# Sheet1.net
KiCad netlist of a schematic drawn in Altium Designer
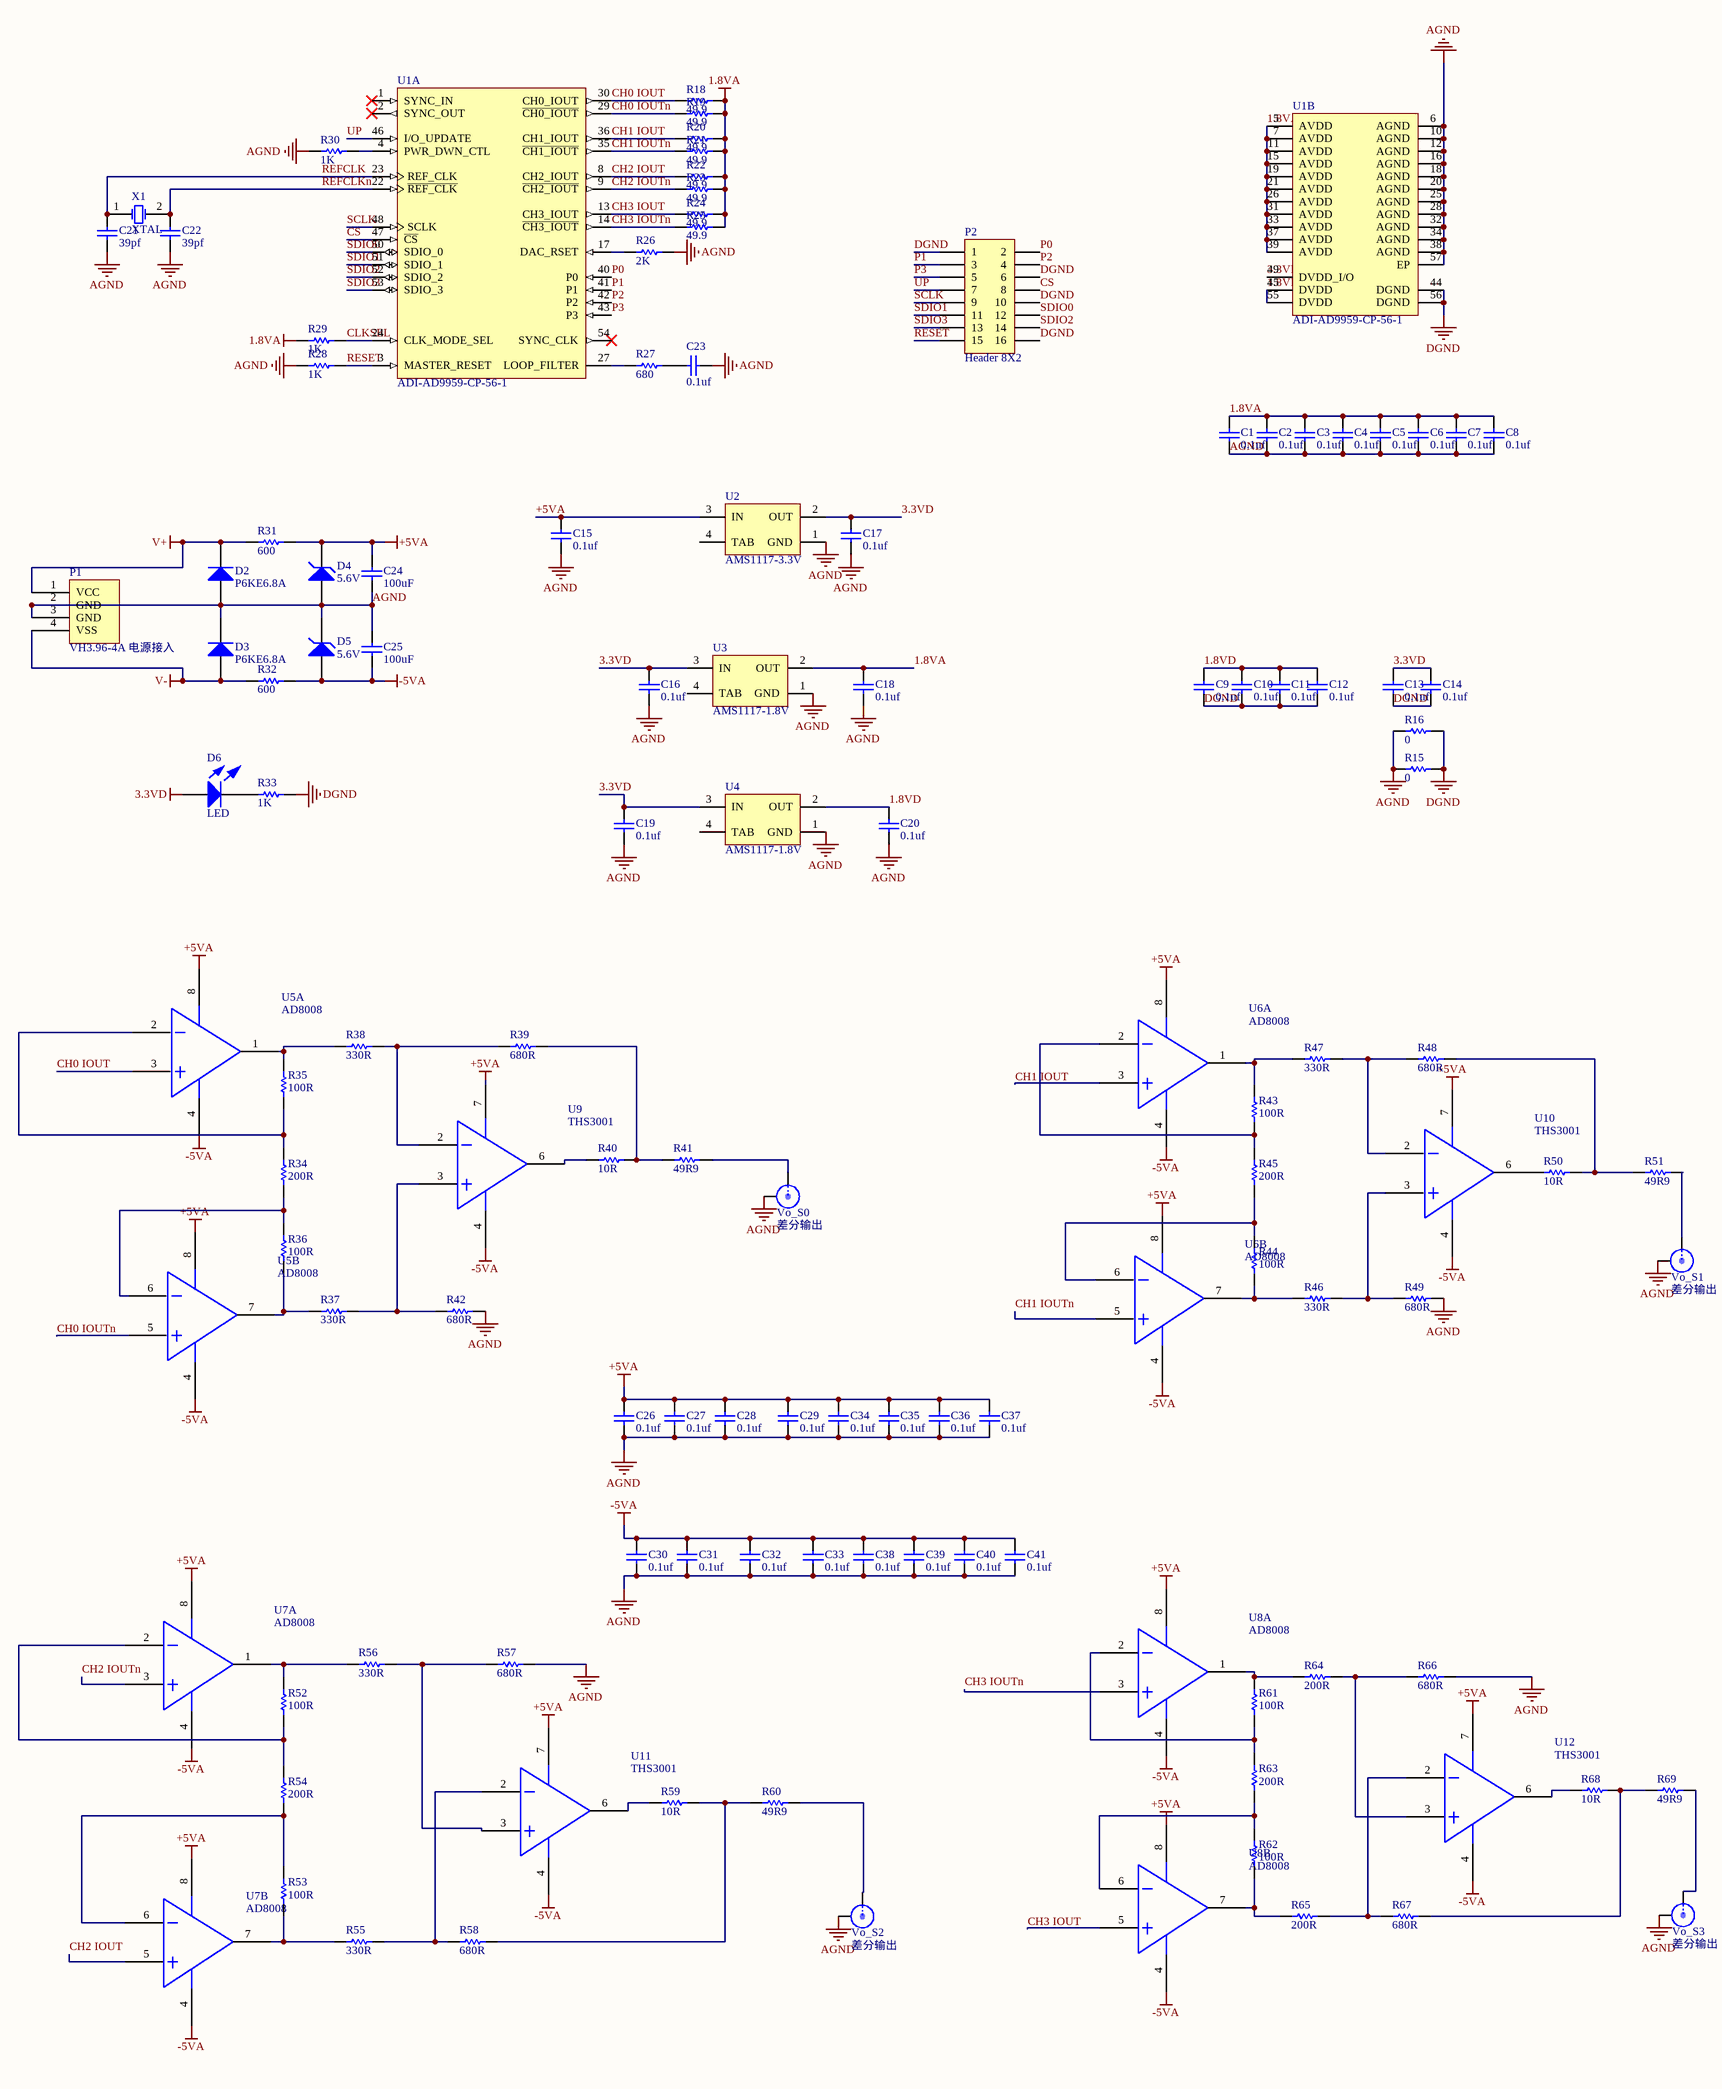
[diagram p0: Sheet1.SchDoc]

(export (version "E")
  (design (tool "Eeschema 10.0.6"))
  (components
    (comp (ref "C1") (value "0.1uf") (footprint "0805") (libsource (lib "Schlib1") (part "Cap")))
    (comp (ref "C2") (value "0.1uf") (footprint "0805") (libsource (lib "Schlib1") (part "Cap")))
    (comp (ref "C3") (value "0.1uf") (footprint "0805") (libsource (lib "Schlib1") (part "Cap")))
    (comp (ref "C4") (value "0.1uf") (footprint "0805") (libsource (lib "Schlib1") (part "Cap")))
    (comp (ref "C5") (value "0.1uf") (footprint "0805") (libsource (lib "Schlib1") (part "Cap")))
    (comp (ref "C6") (value "0.1uf") (footprint "0805") (libsource (lib "Schlib1") (part "Cap")))
    (comp (ref "C7") (value "0.1uf") (footprint "0805") (libsource (lib "Schlib1") (part "Cap")))
    (comp (ref "C8") (value "0.1uf") (footprint "0805") (libsource (lib "Schlib1") (part "Cap")))
    (comp (ref "C9") (value "0.1uf") (footprint "0805") (libsource (lib "Schlib1") (part "Cap")))
    (comp (ref "C10") (value "0.1uf") (footprint "0805") (libsource (lib "Schlib1") (part "Cap")))
    (comp (ref "C11") (value "0.1uf") (footprint "0805") (libsource (lib "Schlib1") (part "Cap")))
    (comp (ref "C12") (value "0.1uf") (footprint "0805") (libsource (lib "Schlib1") (part "Cap")))
    (comp (ref "C13") (value "0.1uf") (footprint "0805") (libsource (lib "Schlib1") (part "Cap")))
    (comp (ref "C14") (value "0.1uf") (footprint "0805") (libsource (lib "Schlib1") (part "Cap")))
    (comp (ref "C15") (value "0.1uf") (footprint "0805") (libsource (lib "Schlib1") (part "Cap")))
    (comp (ref "C16") (value "0.1uf") (footprint "0805") (libsource (lib "Schlib1") (part "Cap")))
    (comp (ref "C17") (value "0.1uf") (footprint "0805") (libsource (lib "Schlib1") (part "Cap")))
    (comp (ref "C18") (value "0.1uf") (footprint "0805") (libsource (lib "Schlib1") (part "Cap")))
    (comp (ref "C19") (value "0.1uf") (footprint "0805") (libsource (lib "Schlib1") (part "Cap")))
    (comp (ref "C20") (value "0.1uf") (footprint "0805") (libsource (lib "Schlib1") (part "Cap")))
    (comp (ref "C21") (value "39pf") (footprint "0805") (libsource (lib "Schlib1") (part "Cap")))
    (comp (ref "C22") (value "39pf") (footprint "0805") (libsource (lib "Schlib1") (part "Cap")))
    (comp (ref "C23") (value "0.1uf") (footprint "0805") (libsource (lib "Schlib1") (part "Cap")))
    (comp (ref "C24") (value "100uF") (footprint "0805") (libsource (lib "Slivy's Library") (part "CAP")))
    (comp (ref "C25") (value "100uF") (footprint "0805") (libsource (lib "Slivy's Library") (part "CAP")))
    (comp (ref "C26") (value "0.1uf") (footprint "0805") (libsource (lib "Schlib1") (part "Cap")))
    (comp (ref "C27") (value "0.1uf") (footprint "0805") (libsource (lib "Schlib1") (part "Cap")))
    (comp (ref "C28") (value "0.1uf") (footprint "0805") (libsource (lib "Schlib1") (part "Cap")))
    (comp (ref "C29") (value "0.1uf") (footprint "0805") (libsource (lib "Schlib1") (part "Cap")))
    (comp (ref "C30") (value "0.1uf") (footprint "0805") (libsource (lib "Schlib1") (part "Cap")))
    (comp (ref "C31") (value "0.1uf") (footprint "0805") (libsource (lib "Schlib1") (part "Cap")))
    (comp (ref "C32") (value "0.1uf") (footprint "0805") (libsource (lib "Schlib1") (part "Cap")))
    (comp (ref "C33") (value "0.1uf") (footprint "0805") (libsource (lib "Schlib1") (part "Cap")))
    (comp (ref "C34") (value "0.1uf") (footprint "0805") (libsource (lib "Schlib1") (part "Cap")))
    (comp (ref "C35") (value "0.1uf") (footprint "0805") (libsource (lib "Schlib1") (part "Cap")))
    (comp (ref "C36") (value "0.1uf") (footprint "0805") (libsource (lib "Schlib1") (part "Cap")))
    (comp (ref "C37") (value "0.1uf") (footprint "0805") (libsource (lib "Schlib1") (part "Cap")))
    (comp (ref "C38") (value "0.1uf") (footprint "0805") (libsource (lib "Schlib1") (part "Cap")))
    (comp (ref "C39") (value "0.1uf") (footprint "0805") (libsource (lib "Schlib1") (part "Cap")))
    (comp (ref "C40") (value "0.1uf") (footprint "0805") (libsource (lib "Schlib1") (part "Cap")))
    (comp (ref "C41") (value "0.1uf") (footprint "0805") (libsource (lib "Schlib1") (part "Cap")))
    (comp (ref "D2")
      (value "P6KE6.8A")
      (footprint "SMA/DO-214AC")
      (libsource (lib "Schlib1") (part "P6KE6.8A"))
    )
    (comp (ref "D3")
      (value "P6KE6.8A")
      (footprint "SMA/DO-214AC")
      (libsource (lib "Schlib1") (part "P6KE6.8A"))
    )
    (comp (ref "D4") (value "5.6V") (footprint "SMA/DO-214AC") (libsource (lib "Schlib1") (part "肖特基-5.6V")))
    (comp (ref "D5") (value "5.6V") (footprint "SMA/DO-214AC") (libsource (lib "Schlib1") (part "肖特基-5.6V")))
    (comp (ref "D6") (value "LED") (footprint "0805") (libsource (lib "Schlib1") (part "LED")))
    (comp (ref "P1")
      (value "VH3.96-4A 电源接入")
      (footprint "VH3.96-4P")
      (libsource (lib "Schlib1") (part "VH3.96-4A"))
    )
    (comp (ref "P2")
      (value "Header 8X2")
      (footprint "HDR2X8")
      (description "Header, 8-Pin, Dual row")
      (fields (field (name "PUBLISHER") "Altium Limited"))
      (libsource (lib "Miscellaneous Connectors") (part "Header 8X2"))
    )
    (comp (ref "R15") (value "0") (footprint "0805") (libsource (lib "Schlib1") (part "Res")))
    (comp (ref "R16") (value "0") (footprint "0805") (libsource (lib "Schlib1") (part "Res")))
    (comp (ref "R18") (value "49.9") (footprint "0805") (libsource (lib "Schlib1") (part "Res")))
    (comp (ref "R19") (value "49.9") (footprint "0805") (libsource (lib "Schlib1") (part "Res")))
    (comp (ref "R20") (value "49.9") (footprint "0805") (libsource (lib "Schlib1") (part "Res")))
    (comp (ref "R21") (value "49.9") (footprint "0805") (libsource (lib "Schlib1") (part "Res")))
    (comp (ref "R22") (value "49.9") (footprint "0805") (libsource (lib "Schlib1") (part "Res")))
    (comp (ref "R23") (value "49.9") (footprint "0805") (libsource (lib "Schlib1") (part "Res")))
    (comp (ref "R24") (value "49.9") (footprint "0805") (libsource (lib "Schlib1") (part "Res")))
    (comp (ref "R25") (value "49.9") (footprint "0805") (libsource (lib "Schlib1") (part "Res")))
    (comp (ref "R26") (value "2K") (footprint "0805") (libsource (lib "Schlib1") (part "Res")))
    (comp (ref "R27") (value "680") (footprint "0805") (libsource (lib "Schlib1") (part "Res")))
    (comp (ref "R28") (value "1K") (footprint "0805") (libsource (lib "Schlib1") (part "Res")))
    (comp (ref "R29") (value "1K") (footprint "0805") (libsource (lib "Schlib1") (part "Res")))
    (comp (ref "R30") (value "1K") (footprint "0805") (libsource (lib "Schlib1") (part "Res")))
    (comp (ref "R31") (value "600") (footprint "0805") (libsource (lib "Schlib1") (part "Res")))
    (comp (ref "R32") (value "600") (footprint "0805") (libsource (lib "Schlib1") (part "Res")))
    (comp (ref "R33") (value "1K") (footprint "0805") (libsource (lib "Schlib1") (part "Res")))
    (comp (ref "R34") (value "200R") (footprint "0805") (libsource (lib "Schlib1") (part "Res")))
    (comp (ref "R35") (value "100R") (footprint "0805") (libsource (lib "Schlib1") (part "Res")))
    (comp (ref "R36") (value "100R") (footprint "0805") (libsource (lib "Schlib1") (part "Res")))
    (comp (ref "R37") (value "330R") (footprint "0805") (libsource (lib "Schlib1") (part "Res")))
    (comp (ref "R38") (value "330R") (footprint "0805") (libsource (lib "Schlib1") (part "Res")))
    (comp (ref "R39") (value "680R") (footprint "0805") (libsource (lib "Schlib1") (part "Res")))
    (comp (ref "R40") (value "10R") (footprint "0805") (libsource (lib "Schlib1") (part "Res")))
    (comp (ref "R41") (value "49R9") (footprint "0805") (libsource (lib "Schlib1") (part "Res")))
    (comp (ref "R42") (value "680R") (footprint "0805") (libsource (lib "Schlib1") (part "Res")))
    (comp (ref "R43") (value "100R") (footprint "0805") (libsource (lib "Schlib1") (part "Res")))
    (comp (ref "R44") (value "100R") (footprint "0805") (libsource (lib "Schlib1") (part "Res")))
    (comp (ref "R45") (value "200R") (footprint "0805") (libsource (lib "Schlib1") (part "Res")))
    (comp (ref "R46") (value "330R") (footprint "0805") (libsource (lib "Schlib1") (part "Res")))
    (comp (ref "R47") (value "330R") (footprint "0805") (libsource (lib "Schlib1") (part "Res")))
    (comp (ref "R48") (value "680R") (footprint "0805") (libsource (lib "Schlib1") (part "Res")))
    (comp (ref "R49") (value "680R") (footprint "0805") (libsource (lib "Schlib1") (part "Res")))
    (comp (ref "R50") (value "10R") (footprint "0805") (libsource (lib "Schlib1") (part "Res")))
    (comp (ref "R51") (value "49R9") (footprint "0805") (libsource (lib "Schlib1") (part "Res")))
    (comp (ref "R52") (value "100R") (footprint "0805") (libsource (lib "Schlib1") (part "Res")))
    (comp (ref "R53") (value "100R") (footprint "0805") (libsource (lib "Schlib1") (part "Res")))
    (comp (ref "R54") (value "200R") (footprint "0805") (libsource (lib "Schlib1") (part "Res")))
    (comp (ref "R55") (value "330R") (footprint "0805") (libsource (lib "Schlib1") (part "Res")))
    (comp (ref "R56") (value "330R") (footprint "0805") (libsource (lib "Schlib1") (part "Res")))
    (comp (ref "R57") (value "680R") (footprint "0805") (libsource (lib "Schlib1") (part "Res")))
    (comp (ref "R58") (value "680R") (footprint "0805") (libsource (lib "Schlib1") (part "Res")))
    (comp (ref "R59") (value "10R") (footprint "0805") (libsource (lib "Schlib1") (part "Res")))
    (comp (ref "R60") (value "49R9") (footprint "0805") (libsource (lib "Schlib1") (part "Res")))
    (comp (ref "R61") (value "100R") (footprint "0805") (libsource (lib "Schlib1") (part "Res")))
    (comp (ref "R62") (value "100R") (footprint "0805") (libsource (lib "Schlib1") (part "Res")))
    (comp (ref "R63") (value "200R") (footprint "0805") (libsource (lib "Schlib1") (part "Res")))
    (comp (ref "R64") (value "200R") (footprint "0805") (libsource (lib "Schlib1") (part "Res")))
    (comp (ref "R65") (value "200R") (footprint "0805") (libsource (lib "Schlib1") (part "Res")))
    (comp (ref "R66") (value "680R") (footprint "0805") (libsource (lib "Schlib1") (part "Res")))
    (comp (ref "R67") (value "680R") (footprint "0805") (libsource (lib "Schlib1") (part "Res")))
    (comp (ref "R68") (value "10R") (footprint "0805") (libsource (lib "Schlib1") (part "Res")))
    (comp (ref "R69") (value "49R9") (footprint "0805") (libsource (lib "Schlib1") (part "Res")))
    (comp (ref "U1")
      (value "ADI-AD9959-CP-56-1")
      (footprint "ADI-CP-56-1_L")
      (libsource (lib "Schlib1") (part "ADI-AD9959-CP-56-1"))
    )
    (comp (ref "U2")
      (value "AMS1117-3.3V")
      (footprint "SOT223")
      (libsource (lib "Schlib1") (part "AMS1117-3.3V"))
    )
    (comp (ref "U3")
      (value "AMS1117-1.8V")
      (footprint "SOT223")
      (libsource (lib "Schlib1") (part "AMS1117-1.8V"))
    )
    (comp (ref "U4")
      (value "AMS1117-1.8V")
      (footprint "SOT223")
      (libsource (lib "Schlib1") (part "AMS1117-1.8V"))
    )
    (comp (ref "U5")
      (value "AD8008")
      (footprint "LC-SOIC-8_150mil")
      (libsource (lib "Schlib1") (part "AD8008"))
    )
    (comp (ref "U6")
      (value "AD8008")
      (footprint "LC-SOIC-8_150mil")
      (libsource (lib "Schlib1") (part "AD8008"))
    )
    (comp (ref "U7")
      (value "AD8008")
      (footprint "LC-SOIC-8_150mil")
      (libsource (lib "Schlib1") (part "AD8008"))
    )
    (comp (ref "U8")
      (value "AD8008")
      (footprint "LC-SOIC-8_150mil")
      (libsource (lib "Schlib1") (part "AD8008"))
    )
    (comp (ref "U9")
      (value "THS3001")
      (footprint "LC-SOIC-8_150mil")
      (libsource (lib "Schlib1") (part "THS3001"))
    )
    (comp (ref "U10")
      (value "THS3001")
      (footprint "LC-SOIC-8_150mil")
      (libsource (lib "Schlib1") (part "THS3001"))
    )
    (comp (ref "U11")
      (value "THS3001")
      (footprint "LC-SOIC-8_150mil")
      (libsource (lib "Schlib1") (part "THS3001"))
    )
    (comp (ref "U12")
      (value "THS3001")
      (footprint "LC-SOIC-8_150mil")
      (libsource (lib "Schlib1") (part "THS3001"))
    )
    (comp (ref "Vo_S0") (value "差分输出") (footprint "SMA-LYING") (libsource (lib "Schlib1") (part "SMA")))
    (comp (ref "Vo_S1") (value "差分输出") (footprint "SMA-LYING") (libsource (lib "Schlib1") (part "SMA")))
    (comp (ref "Vo_S2") (value "差分输出") (footprint "SMA-LYING") (libsource (lib "Schlib1") (part "SMA")))
    (comp (ref "Vo_S3") (value "差分输出") (footprint "SMA-LYING") (libsource (lib "Schlib1") (part "SMA")))
    (comp (ref "X1")
      (value "XTAL")
      (footprint "XAL HC-49S")
      (description "Crystal Oscillator")
      (fields (field (name "PUBLISHER") "Altium Limited"))
      (libsource (lib "Miscellaneous Devices") (part "XTAL"))
    )
  )
  (nets
    (net (code "1") (name "+5VA") (class "Default")
      (node (ref "C15") (pin "2") (pinfunction "2_2") (pintype "passive"))
      (node (ref "C24") (pin "2") (pinfunction "2_2") (pintype "passive"))
      (node (ref "C26") (pin "2") (pinfunction "2_2") (pintype "passive"))
      (node (ref "C27") (pin "2") (pinfunction "2_2") (pintype "passive"))
      (node (ref "C28") (pin "2") (pinfunction "2_2") (pintype "passive"))
      (node (ref "C29") (pin "2") (pinfunction "2_2") (pintype "passive"))
      (node (ref "C34") (pin "2") (pinfunction "2_2") (pintype "passive"))
      (node (ref "C35") (pin "2") (pinfunction "2_2") (pintype "passive"))
      (node (ref "C36") (pin "2") (pinfunction "2_2") (pintype "passive"))
      (node (ref "C37") (pin "2") (pinfunction "2_2") (pintype "passive"))
      (node (ref "D4") (pin "2") (pinfunction "K_2") (pintype "passive"))
      (node (ref "R31") (pin "2") (pinfunction "2_2") (pintype "passive"))
      (node (ref "U10") (pin "7") (pinfunction "IN-_7") (pintype "passive"))
      (node (ref "U11") (pin "7") (pinfunction "IN-_7") (pintype "passive"))
      (node (ref "U12") (pin "7") (pinfunction "IN-_7") (pintype "passive"))
      (node (ref "U2") (pin "3") (pinfunction "IN_3") (pintype "power_in"))
      (node (ref "U5") (pin "8") (pintype "passive"))
      (node (ref "U6") (pin "8") (pintype "passive"))
      (node (ref "U7") (pin "8") (pintype "passive"))
      (node (ref "U8") (pin "8") (pintype "passive"))
      (node (ref "U9") (pin "7") (pinfunction "IN-_7") (pintype "passive"))
    )
    (net (code "2") (name "-5VA") (class "Default")
      (node (ref "C25") (pin "2") (pinfunction "2_2") (pintype "passive"))
      (node (ref "C30") (pin "2") (pinfunction "2_2") (pintype "passive"))
      (node (ref "C31") (pin "2") (pinfunction "2_2") (pintype "passive"))
      (node (ref "C32") (pin "2") (pinfunction "2_2") (pintype "passive"))
      (node (ref "C33") (pin "2") (pinfunction "2_2") (pintype "passive"))
      (node (ref "C38") (pin "2") (pinfunction "2_2") (pintype "passive"))
      (node (ref "C39") (pin "2") (pinfunction "2_2") (pintype "passive"))
      (node (ref "C40") (pin "2") (pinfunction "2_2") (pintype "passive"))
      (node (ref "C41") (pin "2") (pinfunction "2_2") (pintype "passive"))
      (node (ref "D5") (pin "1") (pinfunction "A_1") (pintype "passive"))
      (node (ref "R32") (pin "2") (pinfunction "2_2") (pintype "passive"))
      (node (ref "U10") (pin "4") (pinfunction "IN-_4") (pintype "passive"))
      (node (ref "U11") (pin "4") (pinfunction "IN-_4") (pintype "passive"))
      (node (ref "U12") (pin "4") (pinfunction "IN-_4") (pintype "passive"))
      (node (ref "U5") (pin "4") (pinfunction "IN-_4") (pintype "passive"))
      (node (ref "U6") (pin "4") (pinfunction "IN-_4") (pintype "passive"))
      (node (ref "U7") (pin "4") (pinfunction "IN-_4") (pintype "passive"))
      (node (ref "U8") (pin "4") (pinfunction "IN-_4") (pintype "passive"))
      (node (ref "U9") (pin "4") (pinfunction "IN-_4") (pintype "passive"))
    )
    (net (code "3") (name "/1.8VD") (class "Default")
      (node (ref "C10") (pin "2") (pinfunction "2_2") (pintype "passive"))
      (node (ref "C11") (pin "2") (pinfunction "2_2") (pintype "passive"))
      (node (ref "C12") (pin "2") (pinfunction "2_2") (pintype "passive"))
      (node (ref "C20") (pin "2") (pinfunction "2_2") (pintype "passive"))
      (node (ref "C9") (pin "2") (pinfunction "2_2") (pintype "passive"))
      (node (ref "U1") (pin "45") (pinfunction "DVDD_45") (pintype "power_in"))
      (node (ref "U1") (pin "55") (pinfunction "DVDD_55") (pintype "power_in"))
      (node (ref "U4") (pin "2") (pinfunction "OUT_2") (pintype "power_in"))
    )
    (net (code "4") (name "/CH0 IOUT") (class "Default")
      (node (ref "R18") (pin "1") (pinfunction "1_1") (pintype "passive"))
      (node (ref "U1") (pin "30") (pinfunction "CH0_IOUT_30") (pintype "output"))
      (node (ref "U5") (pin "3") (pinfunction "IN-_3") (pintype "passive"))
    )
    (net (code "5") (name "/CH0 IOUTn") (class "Default")
      (node (ref "R19") (pin "1") (pinfunction "1_1") (pintype "passive"))
      (node (ref "U1") (pin "29") (pinfunction "~{CH0_IOUT}_29") (pintype "output"))
      (node (ref "U5") (pin "5") (pinfunction "IN-_5") (pintype "passive"))
    )
    (net (code "6") (name "/CH1 IOUT") (class "Default")
      (node (ref "R20") (pin "1") (pinfunction "1_1") (pintype "passive"))
      (node (ref "U1") (pin "36") (pinfunction "CH1_IOUT_36") (pintype "output"))
      (node (ref "U6") (pin "3") (pinfunction "IN-_3") (pintype "passive"))
    )
    (net (code "7") (name "/CH1 IOUTn") (class "Default")
      (node (ref "R21") (pin "1") (pinfunction "1_1") (pintype "passive"))
      (node (ref "U1") (pin "35") (pinfunction "~{CH1_IOUT}_35") (pintype "output"))
      (node (ref "U6") (pin "5") (pinfunction "IN-_5") (pintype "passive"))
    )
    (net (code "8") (name "/CH2 IOUT") (class "Default")
      (node (ref "R22") (pin "1") (pinfunction "1_1") (pintype "passive"))
      (node (ref "U1") (pin "8") (pinfunction "CH2_IOUT_8") (pintype "output"))
      (node (ref "U7") (pin "5") (pinfunction "IN-_5") (pintype "passive"))
    )
    (net (code "9") (name "/CH2 IOUTn") (class "Default")
      (node (ref "R23") (pin "1") (pinfunction "1_1") (pintype "passive"))
      (node (ref "U1") (pin "9") (pinfunction "~{CH2_IOUT}_9") (pintype "output"))
      (node (ref "U7") (pin "3") (pinfunction "IN-_3") (pintype "passive"))
    )
    (net (code "10") (name "/CH3 IOUT") (class "Default")
      (node (ref "R24") (pin "1") (pinfunction "1_1") (pintype "passive"))
      (node (ref "U1") (pin "13") (pinfunction "CH3_IOUT_13") (pintype "output"))
      (node (ref "U8") (pin "5") (pinfunction "IN-_5") (pintype "passive"))
    )
    (net (code "11") (name "/CH3 IOUTn") (class "Default")
      (node (ref "R25") (pin "1") (pinfunction "1_1") (pintype "passive"))
      (node (ref "U1") (pin "14") (pinfunction "~{CH3_IOUT}_14") (pintype "output"))
      (node (ref "U8") (pin "3") (pinfunction "IN-_3") (pintype "passive"))
    )
    (net (code "12") (name "/CLKSEL") (class "Default")
      (node (ref "R29") (pin "2") (pinfunction "2_2") (pintype "passive"))
      (node (ref "U1") (pin "24") (pinfunction "CLK_MODE_SEL_24") (pintype "input"))
    )
    (net (code "13") (name "/CS") (class "Default")
      (node (ref "P2") (pin "8") (pinfunction "8_8") (pintype "passive"))
      (node (ref "U1") (pin "47") (pinfunction "~{CS}_47") (pintype "input"))
    )
    (net (code "14") (name "/P0") (class "Default")
      (node (ref "P2") (pin "2") (pinfunction "2_2") (pintype "passive"))
      (node (ref "U1") (pin "40") (pinfunction "P0_40") (pintype "input"))
    )
    (net (code "15") (name "/P1") (class "Default")
      (node (ref "P2") (pin "3") (pinfunction "3_3") (pintype "passive"))
      (node (ref "U1") (pin "41") (pinfunction "P1_41") (pintype "input"))
    )
    (net (code "16") (name "/P2") (class "Default")
      (node (ref "P2") (pin "4") (pinfunction "4_4") (pintype "passive"))
      (node (ref "U1") (pin "42") (pinfunction "P2_42") (pintype "input"))
    )
    (net (code "17") (name "/P3") (class "Default")
      (node (ref "P2") (pin "5") (pinfunction "5_5") (pintype "passive"))
      (node (ref "U1") (pin "43") (pinfunction "P3_43") (pintype "input"))
    )
    (net (code "18") (name "/REFCLK") (class "Default")
      (node (ref "C21") (pin "2") (pinfunction "2_2") (pintype "passive"))
      (node (ref "U1") (pin "23") (pinfunction "REF_CLK_23") (pintype "input"))
      (node (ref "X1") (pin "1") (pinfunction "OSC1_1") (pintype "passive"))
    )
    (net (code "19") (name "/REFCLKn") (class "Default")
      (node (ref "C22") (pin "2") (pinfunction "2_2") (pintype "passive"))
      (node (ref "U1") (pin "22") (pinfunction "~{REF_CLK}_22") (pintype "input"))
      (node (ref "X1") (pin "2") (pinfunction "OSC2_2") (pintype "passive"))
    )
    (net (code "20") (name "/RESET") (class "Default")
      (node (ref "P2") (pin "15") (pinfunction "15_15") (pintype "passive"))
      (node (ref "R28") (pin "2") (pinfunction "2_2") (pintype "passive"))
      (node (ref "U1") (pin "3") (pinfunction "MASTER_RESET_3") (pintype "input"))
    )
    (net (code "21") (name "/SCLK") (class "Default")
      (node (ref "P2") (pin "9") (pinfunction "9_9") (pintype "passive"))
      (node (ref "U1") (pin "48") (pinfunction "SCLK_48") (pintype "input"))
    )
    (net (code "22") (name "/SDIO0") (class "Default")
      (node (ref "P2") (pin "12") (pinfunction "12_12") (pintype "passive"))
      (node (ref "U1") (pin "50") (pinfunction "SDIO_0_50") (pintype "bidirectional"))
    )
    (net (code "23") (name "/SDIO1") (class "Default")
      (node (ref "P2") (pin "11") (pinfunction "11_11") (pintype "passive"))
      (node (ref "U1") (pin "51") (pinfunction "SDIO_1_51") (pintype "bidirectional"))
    )
    (net (code "24") (name "/SDIO2") (class "Default")
      (node (ref "P2") (pin "14") (pinfunction "14_14") (pintype "passive"))
      (node (ref "U1") (pin "52") (pinfunction "SDIO_2_52") (pintype "bidirectional"))
    )
    (net (code "25") (name "/SDIO3") (class "Default")
      (node (ref "P2") (pin "13") (pinfunction "13_13") (pintype "passive"))
      (node (ref "U1") (pin "53") (pinfunction "SDIO_3_53") (pintype "bidirectional"))
    )
    (net (code "26") (name "/UP") (class "Default")
      (node (ref "P2") (pin "7") (pinfunction "7_7") (pintype "passive"))
      (node (ref "U1") (pin "46") (pinfunction "I/O_UPDATE_46") (pintype "input"))
    )
    (net (code "27") (name "1.8VA") (class "Default")
      (node (ref "C1") (pin "2") (pinfunction "2_2") (pintype "passive"))
      (node (ref "C18") (pin "2") (pinfunction "2_2") (pintype "passive"))
      (node (ref "C2") (pin "2") (pinfunction "2_2") (pintype "passive"))
      (node (ref "C3") (pin "2") (pinfunction "2_2") (pintype "passive"))
      (node (ref "C4") (pin "2") (pinfunction "2_2") (pintype "passive"))
      (node (ref "C5") (pin "2") (pinfunction "2_2") (pintype "passive"))
      (node (ref "C6") (pin "2") (pinfunction "2_2") (pintype "passive"))
      (node (ref "C7") (pin "2") (pinfunction "2_2") (pintype "passive"))
      (node (ref "C8") (pin "2") (pinfunction "2_2") (pintype "passive"))
      (node (ref "R18") (pin "2") (pinfunction "2_2") (pintype "passive"))
      (node (ref "R19") (pin "2") (pinfunction "2_2") (pintype "passive"))
      (node (ref "R20") (pin "2") (pinfunction "2_2") (pintype "passive"))
      (node (ref "R21") (pin "2") (pinfunction "2_2") (pintype "passive"))
      (node (ref "R22") (pin "2") (pinfunction "2_2") (pintype "passive"))
      (node (ref "R23") (pin "2") (pinfunction "2_2") (pintype "passive"))
      (node (ref "R24") (pin "2") (pinfunction "2_2") (pintype "passive"))
      (node (ref "R25") (pin "2") (pinfunction "2_2") (pintype "passive"))
      (node (ref "R29") (pin "1") (pinfunction "1_1") (pintype "passive"))
      (node (ref "U1") (pin "11") (pinfunction "AVDD_11") (pintype "power_in"))
      (node (ref "U1") (pin "15") (pinfunction "AVDD_15") (pintype "power_in"))
      (node (ref "U1") (pin "19") (pinfunction "AVDD_19") (pintype "power_in"))
      (node (ref "U1") (pin "21") (pinfunction "AVDD_21") (pintype "power_in"))
      (node (ref "U1") (pin "26") (pinfunction "AVDD_26") (pintype "power_in"))
      (node (ref "U1") (pin "31") (pinfunction "AVDD_31") (pintype "power_in"))
      (node (ref "U1") (pin "33") (pinfunction "AVDD_33") (pintype "power_in"))
      (node (ref "U1") (pin "37") (pinfunction "AVDD_37") (pintype "power_in"))
      (node (ref "U1") (pin "39") (pinfunction "AVDD_39") (pintype "power_in"))
      (node (ref "U1") (pin "5") (pinfunction "AVDD_5") (pintype "power_in"))
      (node (ref "U1") (pin "7") (pinfunction "AVDD_7") (pintype "power_in"))
      (node (ref "U3") (pin "2") (pinfunction "OUT_2") (pintype "power_in"))
    )
    (net (code "28") (name "3.3VD") (class "Default")
      (node (ref "C13") (pin "2") (pinfunction "2_2") (pintype "passive"))
      (node (ref "C14") (pin "2") (pinfunction "2_2") (pintype "passive"))
      (node (ref "C16") (pin "2") (pinfunction "2_2") (pintype "passive"))
      (node (ref "C17") (pin "2") (pinfunction "2_2") (pintype "passive"))
      (node (ref "C19") (pin "2") (pinfunction "2_2") (pintype "passive"))
      (node (ref "D6") (pin "1") (pinfunction "A_1") (pintype "passive"))
      (node (ref "U1") (pin "49") (pinfunction "DVDD_I/O_49") (pintype "power_in"))
      (node (ref "U2") (pin "2") (pinfunction "OUT_2") (pintype "power_in"))
      (node (ref "U3") (pin "3") (pinfunction "IN_3") (pintype "power_in"))
      (node (ref "U4") (pin "3") (pinfunction "IN_3") (pintype "power_in"))
    )
    (net (code "29") (name "AGND") (class "Default")
      (node (ref "C1") (pin "1") (pinfunction "1_1") (pintype "passive"))
      (node (ref "C15") (pin "1") (pinfunction "1_1") (pintype "passive"))
      (node (ref "C16") (pin "1") (pinfunction "1_1") (pintype "passive"))
      (node (ref "C17") (pin "1") (pinfunction "1_1") (pintype "passive"))
      (node (ref "C18") (pin "1") (pinfunction "1_1") (pintype "passive"))
      (node (ref "C19") (pin "1") (pinfunction "1_1") (pintype "passive"))
      (node (ref "C2") (pin "1") (pinfunction "1_1") (pintype "passive"))
      (node (ref "C20") (pin "1") (pinfunction "1_1") (pintype "passive"))
      (node (ref "C21") (pin "1") (pinfunction "1_1") (pintype "passive"))
      (node (ref "C22") (pin "1") (pinfunction "1_1") (pintype "passive"))
      (node (ref "C23") (pin "2") (pinfunction "2_2") (pintype "passive"))
      (node (ref "C24") (pin "1") (pinfunction "1_1") (pintype "passive"))
      (node (ref "C25") (pin "1") (pinfunction "1_1") (pintype "passive"))
      (node (ref "C26") (pin "1") (pinfunction "1_1") (pintype "passive"))
      (node (ref "C27") (pin "1") (pinfunction "1_1") (pintype "passive"))
      (node (ref "C28") (pin "1") (pinfunction "1_1") (pintype "passive"))
      (node (ref "C29") (pin "1") (pinfunction "1_1") (pintype "passive"))
      (node (ref "C3") (pin "1") (pinfunction "1_1") (pintype "passive"))
      (node (ref "C30") (pin "1") (pinfunction "1_1") (pintype "passive"))
      (node (ref "C31") (pin "1") (pinfunction "1_1") (pintype "passive"))
      (node (ref "C32") (pin "1") (pinfunction "1_1") (pintype "passive"))
      (node (ref "C33") (pin "1") (pinfunction "1_1") (pintype "passive"))
      (node (ref "C34") (pin "1") (pinfunction "1_1") (pintype "passive"))
      (node (ref "C35") (pin "1") (pinfunction "1_1") (pintype "passive"))
      (node (ref "C36") (pin "1") (pinfunction "1_1") (pintype "passive"))
      (node (ref "C37") (pin "1") (pinfunction "1_1") (pintype "passive"))
      (node (ref "C38") (pin "1") (pinfunction "1_1") (pintype "passive"))
      (node (ref "C39") (pin "1") (pinfunction "1_1") (pintype "passive"))
      (node (ref "C4") (pin "1") (pinfunction "1_1") (pintype "passive"))
      (node (ref "C40") (pin "1") (pinfunction "1_1") (pintype "passive"))
      (node (ref "C41") (pin "1") (pinfunction "1_1") (pintype "passive"))
      (node (ref "C5") (pin "1") (pinfunction "1_1") (pintype "passive"))
      (node (ref "C6") (pin "1") (pinfunction "1_1") (pintype "passive"))
      (node (ref "C7") (pin "1") (pinfunction "1_1") (pintype "passive"))
      (node (ref "C8") (pin "1") (pinfunction "1_1") (pintype "passive"))
      (node (ref "D2") (pin "1") (pinfunction "A_1") (pintype "passive"))
      (node (ref "D3") (pin "2") (pinfunction "K_2") (pintype "passive"))
      (node (ref "D4") (pin "1") (pinfunction "A_1") (pintype "passive"))
      (node (ref "D5") (pin "2") (pinfunction "K_2") (pintype "passive"))
      (node (ref "P1") (pin "2") (pinfunction "GND_2") (pintype "passive"))
      (node (ref "P1") (pin "3") (pinfunction "GND_3") (pintype "passive"))
      (node (ref "R15") (pin "1") (pinfunction "1_1") (pintype "passive"))
      (node (ref "R16") (pin "1") (pinfunction "1_1") (pintype "passive"))
      (node (ref "R26") (pin "2") (pinfunction "2_2") (pintype "passive"))
      (node (ref "R28") (pin "1") (pinfunction "1_1") (pintype "passive"))
      (node (ref "R30") (pin "1") (pinfunction "1_1") (pintype "passive"))
      (node (ref "R42") (pin "2") (pinfunction "2_2") (pintype "passive"))
      (node (ref "R49") (pin "1") (pinfunction "1_1") (pintype "passive"))
      (node (ref "R57") (pin "1") (pinfunction "1_1") (pintype "passive"))
      (node (ref "R66") (pin "1") (pinfunction "1_1") (pintype "passive"))
      (node (ref "U1") (pin "10") (pinfunction "AGND_10") (pintype "power_in"))
      (node (ref "U1") (pin "12") (pinfunction "AGND_12") (pintype "power_in"))
      (node (ref "U1") (pin "16") (pinfunction "AGND_16") (pintype "power_in"))
      (node (ref "U1") (pin "18") (pinfunction "AGND_18") (pintype "power_in"))
      (node (ref "U1") (pin "20") (pinfunction "AGND_20") (pintype "power_in"))
      (node (ref "U1") (pin "25") (pinfunction "AGND_25") (pintype "power_in"))
      (node (ref "U1") (pin "28") (pinfunction "AGND_28") (pintype "power_in"))
      (node (ref "U1") (pin "32") (pinfunction "AGND_32") (pintype "power_in"))
      (node (ref "U1") (pin "34") (pinfunction "AGND_34") (pintype "power_in"))
      (node (ref "U1") (pin "38") (pinfunction "AGND_38") (pintype "power_in"))
      (node (ref "U1") (pin "57") (pinfunction "EP_57") (pintype "power_in"))
      (node (ref "U1") (pin "6") (pinfunction "AGND_6") (pintype "power_in"))
      (node (ref "U2") (pin "1") (pinfunction "GND_1") (pintype "power_in"))
      (node (ref "U3") (pin "1") (pinfunction "GND_1") (pintype "power_in"))
      (node (ref "U4") (pin "1") (pinfunction "GND_1") (pintype "power_in"))
      (node (ref "Vo_S0") (pin "1") (pinfunction "1_1") (pintype "passive"))
      (node (ref "Vo_S1") (pin "1") (pinfunction "1_1") (pintype "passive"))
      (node (ref "Vo_S2") (pin "1") (pinfunction "1_1") (pintype "passive"))
      (node (ref "Vo_S3") (pin "1") (pinfunction "1_1") (pintype "passive"))
    )
    (net (code "30") (name "DGND") (class "Default")
      (node (ref "C10") (pin "1") (pinfunction "1_1") (pintype "passive"))
      (node (ref "C11") (pin "1") (pinfunction "1_1") (pintype "passive"))
      (node (ref "C12") (pin "1") (pinfunction "1_1") (pintype "passive"))
      (node (ref "C13") (pin "1") (pinfunction "1_1") (pintype "passive"))
      (node (ref "C14") (pin "1") (pinfunction "1_1") (pintype "passive"))
      (node (ref "C9") (pin "1") (pinfunction "1_1") (pintype "passive"))
      (node (ref "P2") (pin "1") (pinfunction "1_1") (pintype "passive"))
      (node (ref "P2") (pin "10") (pinfunction "10_10") (pintype "passive"))
      (node (ref "P2") (pin "16") (pinfunction "16_16") (pintype "passive"))
      (node (ref "P2") (pin "6") (pinfunction "6_6") (pintype "passive"))
      (node (ref "R15") (pin "2") (pinfunction "2_2") (pintype "passive"))
      (node (ref "R16") (pin "2") (pinfunction "2_2") (pintype "passive"))
      (node (ref "R33") (pin "2") (pinfunction "2_2") (pintype "passive"))
      (node (ref "U1") (pin "44") (pinfunction "DGND_44") (pintype "power_in"))
      (node (ref "U1") (pin "56") (pinfunction "DGND_56") (pintype "power_in"))
    )
    (net (code "31") (name "Net-(C23-Pad1)") (class "Default")
      (node (ref "C23") (pin "1") (pinfunction "1_1") (pintype "passive"))
      (node (ref "R27") (pin "2") (pinfunction "2_2") (pintype "passive"))
    )
    (net (code "32") (name "Net-(D6-K)") (class "Default")
      (node (ref "D6") (pin "2") (pinfunction "K_2") (pintype "passive"))
      (node (ref "R33") (pin "1") (pinfunction "1_1") (pintype "passive"))
    )
    (net (code "33") (name "Net-(R34-Pad1)") (class "Default")
      (node (ref "R34") (pin "1") (pinfunction "1_1") (pintype "passive"))
      (node (ref "R36") (pin "1") (pinfunction "1_1") (pintype "passive"))
      (node (ref "U5") (pin "6") (pinfunction "IN-_6") (pintype "passive"))
    )
    (net (code "34") (name "Net-(R34-Pad2)") (class "Default")
      (node (ref "R34") (pin "2") (pinfunction "2_2") (pintype "passive"))
      (node (ref "R35") (pin "2") (pinfunction "2_2") (pintype "passive"))
      (node (ref "U5") (pin "2") (pinfunction "IN-_2") (pintype "passive"))
    )
    (net (code "35") (name "Net-(R35-Pad1)") (class "Default")
      (node (ref "R35") (pin "1") (pinfunction "1_1") (pintype "passive"))
      (node (ref "R38") (pin "1") (pinfunction "1_1") (pintype "passive"))
      (node (ref "U5") (pin "1") (pinfunction "IN-_1") (pintype "passive"))
    )
    (net (code "36") (name "Net-(R36-Pad2)") (class "Default")
      (node (ref "R36") (pin "2") (pinfunction "2_2") (pintype "passive"))
      (node (ref "R37") (pin "1") (pinfunction "1_1") (pintype "passive"))
      (node (ref "U5") (pin "7") (pinfunction "IN-_7") (pintype "passive"))
    )
    (net (code "37") (name "Net-(R37-Pad2)") (class "Default")
      (node (ref "R37") (pin "2") (pinfunction "2_2") (pintype "passive"))
      (node (ref "R42") (pin "1") (pinfunction "1_1") (pintype "passive"))
      (node (ref "U9") (pin "3") (pinfunction "IN-_3") (pintype "passive"))
    )
    (net (code "38") (name "Net-(R38-Pad2)") (class "Default")
      (node (ref "R38") (pin "2") (pinfunction "2_2") (pintype "passive"))
      (node (ref "R39") (pin "1") (pinfunction "1_1") (pintype "passive"))
      (node (ref "U9") (pin "2") (pinfunction "IN-_2") (pintype "passive"))
    )
    (net (code "39") (name "Net-(R39-Pad2)") (class "Default")
      (node (ref "R39") (pin "2") (pinfunction "2_2") (pintype "passive"))
      (node (ref "R40") (pin "2") (pinfunction "2_2") (pintype "passive"))
      (node (ref "R41") (pin "1") (pinfunction "1_1") (pintype "passive"))
    )
    (net (code "40") (name "Net-(R40-Pad1)") (class "Default")
      (node (ref "R40") (pin "1") (pinfunction "1_1") (pintype "passive"))
      (node (ref "U9") (pin "6") (pinfunction "IN-_6") (pintype "passive"))
    )
    (net (code "41") (name "Net-(R41-Pad2)") (class "Default")
      (node (ref "R41") (pin "2") (pinfunction "2_2") (pintype "passive"))
      (node (ref "Vo_S0") (pin "0") (pinfunction "0_0") (pintype "passive"))
    )
    (net (code "42") (name "Net-(R43-Pad1)") (class "Default")
      (node (ref "R43") (pin "1") (pinfunction "1_1") (pintype "passive"))
      (node (ref "R45") (pin "2") (pinfunction "2_2") (pintype "passive"))
      (node (ref "U6") (pin "2") (pinfunction "IN-_2") (pintype "passive"))
    )
    (net (code "43") (name "Net-(R43-Pad2)") (class "Default")
      (node (ref "R43") (pin "2") (pinfunction "2_2") (pintype "passive"))
      (node (ref "R47") (pin "2") (pinfunction "2_2") (pintype "passive"))
      (node (ref "U6") (pin "1") (pinfunction "IN-_1") (pintype "passive"))
    )
    (net (code "44") (name "Net-(R44-Pad1)") (class "Default")
      (node (ref "R44") (pin "1") (pinfunction "1_1") (pintype "passive"))
      (node (ref "R46") (pin "2") (pinfunction "2_2") (pintype "passive"))
      (node (ref "U6") (pin "7") (pinfunction "IN-_7") (pintype "passive"))
    )
    (net (code "45") (name "Net-(R44-Pad2)") (class "Default")
      (node (ref "R44") (pin "2") (pinfunction "2_2") (pintype "passive"))
      (node (ref "R45") (pin "1") (pinfunction "1_1") (pintype "passive"))
      (node (ref "U6") (pin "6") (pinfunction "IN-_6") (pintype "passive"))
    )
    (net (code "46") (name "Net-(R46-Pad1)") (class "Default")
      (node (ref "R46") (pin "1") (pinfunction "1_1") (pintype "passive"))
      (node (ref "R49") (pin "2") (pinfunction "2_2") (pintype "passive"))
      (node (ref "U10") (pin "3") (pinfunction "IN-_3") (pintype "passive"))
    )
    (net (code "47") (name "Net-(R47-Pad1)") (class "Default")
      (node (ref "R47") (pin "1") (pinfunction "1_1") (pintype "passive"))
      (node (ref "R48") (pin "2") (pinfunction "2_2") (pintype "passive"))
      (node (ref "U10") (pin "2") (pinfunction "IN-_2") (pintype "passive"))
    )
    (net (code "48") (name "Net-(R48-Pad1)") (class "Default")
      (node (ref "R48") (pin "1") (pinfunction "1_1") (pintype "passive"))
      (node (ref "R50") (pin "1") (pinfunction "1_1") (pintype "passive"))
      (node (ref "R51") (pin "2") (pinfunction "2_2") (pintype "passive"))
    )
    (net (code "49") (name "Net-(R50-Pad2)") (class "Default")
      (node (ref "R50") (pin "2") (pinfunction "2_2") (pintype "passive"))
      (node (ref "U10") (pin "6") (pinfunction "IN-_6") (pintype "passive"))
    )
    (net (code "50") (name "Net-(R51-Pad1)") (class "Default")
      (node (ref "R51") (pin "1") (pinfunction "1_1") (pintype "passive"))
      (node (ref "Vo_S1") (pin "0") (pinfunction "0_0") (pintype "passive"))
    )
    (net (code "51") (name "Net-(R52-Pad1)") (class "Default")
      (node (ref "R52") (pin "1") (pinfunction "1_1") (pintype "passive"))
      (node (ref "R54") (pin "2") (pinfunction "2_2") (pintype "passive"))
      (node (ref "U7") (pin "2") (pinfunction "IN-_2") (pintype "passive"))
    )
    (net (code "52") (name "Net-(R52-Pad2)") (class "Default")
      (node (ref "R52") (pin "2") (pinfunction "2_2") (pintype "passive"))
      (node (ref "R56") (pin "2") (pinfunction "2_2") (pintype "passive"))
      (node (ref "U7") (pin "1") (pinfunction "IN-_1") (pintype "passive"))
    )
    (net (code "53") (name "Net-(R53-Pad1)") (class "Default")
      (node (ref "R53") (pin "1") (pinfunction "1_1") (pintype "passive"))
      (node (ref "R55") (pin "2") (pinfunction "2_2") (pintype "passive"))
      (node (ref "U7") (pin "7") (pinfunction "IN-_7") (pintype "passive"))
    )
    (net (code "54") (name "Net-(R53-Pad2)") (class "Default")
      (node (ref "R53") (pin "2") (pinfunction "2_2") (pintype "passive"))
      (node (ref "R54") (pin "1") (pinfunction "1_1") (pintype "passive"))
      (node (ref "U7") (pin "6") (pinfunction "IN-_6") (pintype "passive"))
    )
    (net (code "55") (name "Net-(R55-Pad1)") (class "Default")
      (node (ref "R55") (pin "1") (pinfunction "1_1") (pintype "passive"))
      (node (ref "R58") (pin "2") (pinfunction "2_2") (pintype "passive"))
      (node (ref "U11") (pin "2") (pinfunction "IN-_2") (pintype "passive"))
    )
    (net (code "56") (name "Net-(R56-Pad1)") (class "Default")
      (node (ref "R56") (pin "1") (pinfunction "1_1") (pintype "passive"))
      (node (ref "R57") (pin "2") (pinfunction "2_2") (pintype "passive"))
      (node (ref "U11") (pin "3") (pinfunction "IN-_3") (pintype "passive"))
    )
    (net (code "57") (name "Net-(R58-Pad1)") (class "Default")
      (node (ref "R58") (pin "1") (pinfunction "1_1") (pintype "passive"))
      (node (ref "R59") (pin "1") (pinfunction "1_1") (pintype "passive"))
      (node (ref "R60") (pin "2") (pinfunction "2_2") (pintype "passive"))
    )
    (net (code "58") (name "Net-(R59-Pad2)") (class "Default")
      (node (ref "R59") (pin "2") (pinfunction "2_2") (pintype "passive"))
      (node (ref "U11") (pin "6") (pinfunction "IN-_6") (pintype "passive"))
    )
    (net (code "59") (name "Net-(R60-Pad1)") (class "Default")
      (node (ref "R60") (pin "1") (pinfunction "1_1") (pintype "passive"))
      (node (ref "Vo_S2") (pin "0") (pinfunction "0_0") (pintype "passive"))
    )
    (net (code "60") (name "Net-(R61-Pad1)") (class "Default")
      (node (ref "R61") (pin "1") (pinfunction "1_1") (pintype "passive"))
      (node (ref "R63") (pin "2") (pinfunction "2_2") (pintype "passive"))
      (node (ref "U8") (pin "2") (pinfunction "IN-_2") (pintype "passive"))
    )
    (net (code "61") (name "Net-(R61-Pad2)") (class "Default")
      (node (ref "R61") (pin "2") (pinfunction "2_2") (pintype "passive"))
      (node (ref "R64") (pin "2") (pinfunction "2_2") (pintype "passive"))
      (node (ref "U8") (pin "1") (pinfunction "IN-_1") (pintype "passive"))
    )
    (net (code "62") (name "Net-(R62-Pad1)") (class "Default")
      (node (ref "R62") (pin "1") (pinfunction "1_1") (pintype "passive"))
      (node (ref "R65") (pin "2") (pinfunction "2_2") (pintype "passive"))
      (node (ref "U8") (pin "7") (pinfunction "IN-_7") (pintype "passive"))
    )
    (net (code "63") (name "Net-(R62-Pad2)") (class "Default")
      (node (ref "R62") (pin "2") (pinfunction "2_2") (pintype "passive"))
      (node (ref "R63") (pin "1") (pinfunction "1_1") (pintype "passive"))
      (node (ref "U8") (pin "6") (pinfunction "IN-_6") (pintype "passive"))
    )
    (net (code "64") (name "Net-(R64-Pad1)") (class "Default")
      (node (ref "R64") (pin "1") (pinfunction "1_1") (pintype "passive"))
      (node (ref "R66") (pin "2") (pinfunction "2_2") (pintype "passive"))
      (node (ref "U12") (pin "3") (pinfunction "IN-_3") (pintype "passive"))
    )
    (net (code "65") (name "Net-(R65-Pad1)") (class "Default")
      (node (ref "R65") (pin "1") (pinfunction "1_1") (pintype "passive"))
      (node (ref "R67") (pin "2") (pinfunction "2_2") (pintype "passive"))
      (node (ref "U12") (pin "2") (pinfunction "IN-_2") (pintype "passive"))
    )
    (net (code "66") (name "Net-(R67-Pad1)") (class "Default")
      (node (ref "R67") (pin "1") (pinfunction "1_1") (pintype "passive"))
      (node (ref "R68") (pin "1") (pinfunction "1_1") (pintype "passive"))
      (node (ref "R69") (pin "2") (pinfunction "2_2") (pintype "passive"))
    )
    (net (code "67") (name "Net-(R68-Pad2)") (class "Default")
      (node (ref "R68") (pin "2") (pinfunction "2_2") (pintype "passive"))
      (node (ref "U12") (pin "6") (pinfunction "IN-_6") (pintype "passive"))
    )
    (net (code "68") (name "Net-(R69-Pad1)") (class "Default")
      (node (ref "R69") (pin "1") (pinfunction "1_1") (pintype "passive"))
      (node (ref "Vo_S3") (pin "0") (pinfunction "0_0") (pintype "passive"))
    )
    (net (code "69") (name "Net-(U1A-DAC_RSET)") (class "Default")
      (node (ref "R26") (pin "1") (pinfunction "1_1") (pintype "passive"))
      (node (ref "U1") (pin "17") (pinfunction "DAC_RSET_17") (pintype "input"))
    )
    (net (code "70") (name "Net-(U1A-LOOP_FILTER)") (class "Default")
      (node (ref "R27") (pin "1") (pinfunction "1_1") (pintype "passive"))
      (node (ref "U1") (pin "27") (pinfunction "LOOP_FILTER_27") (pintype "passive"))
    )
    (net (code "71") (name "Net-(U1A-PWR_DWN_CTL)") (class "Default")
      (node (ref "R30") (pin "2") (pinfunction "2_2") (pintype "passive"))
      (node (ref "U1") (pin "4") (pinfunction "PWR_DWN_CTL_4") (pintype "input"))
    )
    (net (code "72") (name "V+") (class "Default")
      (node (ref "D2") (pin "2") (pinfunction "K_2") (pintype "passive"))
      (node (ref "P1") (pin "1") (pinfunction "VCC_1") (pintype "passive"))
      (node (ref "R31") (pin "1") (pinfunction "1_1") (pintype "passive"))
    )
    (net (code "73") (name "V-") (class "Default")
      (node (ref "D3") (pin "1") (pinfunction "A_1") (pintype "passive"))
      (node (ref "P1") (pin "4") (pinfunction "VSS_4") (pintype "passive"))
      (node (ref "R32") (pin "1") (pinfunction "1_1") (pintype "passive"))
    )
    (net (code "74") (name "unconnected-(U1A-SYNC_CLK-Pad54)") (class "Default")
      (node (ref "U1") (pin "54") (pinfunction "SYNC_CLK_54") (pintype "output+no_connect"))
    )
    (net (code "75") (name "unconnected-(U1A-SYNC_IN-Pad1)") (class "Default")
      (node (ref "U1") (pin "1") (pinfunction "SYNC_IN_1") (pintype "input+no_connect"))
    )
    (net (code "76") (name "unconnected-(U1A-SYNC_OUT-Pad2)") (class "Default")
      (node (ref "U1") (pin "2") (pinfunction "SYNC_OUT_2") (pintype "output+no_connect"))
    )
    (net (code "77") (name "unconnected-(U2-TAB-Pad4)") (class "Default")
      (node (ref "U2") (pin "4") (pinfunction "TAB_4") (pintype "power_in"))
    )
    (net (code "78") (name "unconnected-(U3-TAB-Pad4)") (class "Default")
      (node (ref "U3") (pin "4") (pinfunction "TAB_4") (pintype "power_in"))
    )
    (net (code "79") (name "unconnected-(U4-TAB-Pad4)") (class "Default")
      (node (ref "U4") (pin "4") (pinfunction "TAB_4") (pintype "power_in"))
    )
  )
)
